# OSER_RFID_RFIDHub.net
KiCad netlist of a schematic drawn in EAGLE
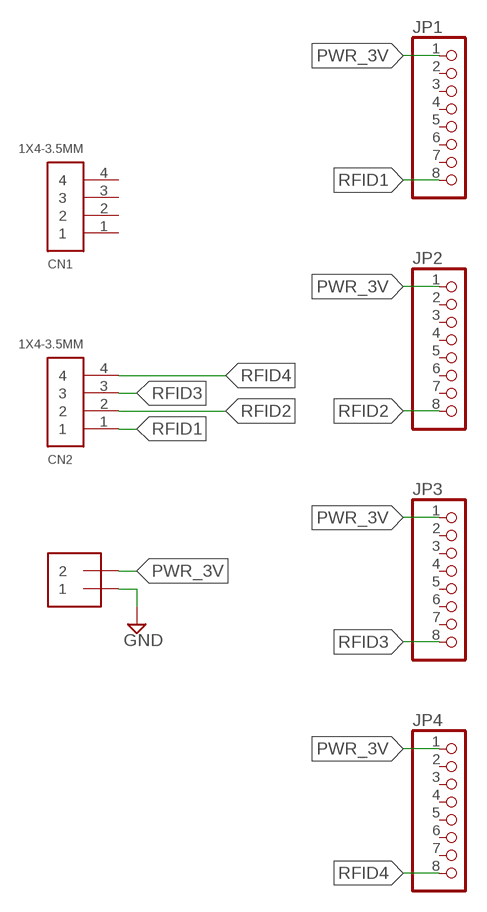
[diagram p0: schematic, sheet 1]

(export (version "E")
  (design (tool "Eeschema 10.0.6"))
  (components
    (comp (ref "CN1")
      (value "1X4-3.5MM")
      (footprint "eagle-import:1X04-3.5MM")
      (libsource (lib "eagle-import") (part "1X4-3.5MM"))
    )
    (comp (ref "CN2")
      (value "1X4-3.5MM")
      (footprint "eagle-import:1X04-3.5MM")
      (libsource (lib "eagle-import") (part "1X4-3.5MM"))
    )
    (comp (ref "J1")
      (value "1X2-3.5MM")
      (footprint "eagle-import:1X2-3.5MM")
      (libsource (lib "eagle-import") (part "1X2-3.5MM"))
    )
    (comp (ref "JP1")
      (value "PINHD-1X8BIG")
      (footprint "eagle-import:1X08-BIG")
      (libsource (lib "eagle-import") (part "PINHD-1X8BIG"))
    )
    (comp (ref "JP2")
      (value "PINHD-1X8BIG")
      (footprint "eagle-import:1X08-BIG")
      (libsource (lib "eagle-import") (part "PINHD-1X8BIG"))
    )
    (comp (ref "JP3")
      (value "PINHD-1X8BIG")
      (footprint "eagle-import:1X08-BIG")
      (libsource (lib "eagle-import") (part "PINHD-1X8BIG"))
    )
    (comp (ref "JP4")
      (value "PINHD-1X8BIG")
      (footprint "eagle-import:1X08-BIG")
      (libsource (lib "eagle-import") (part "PINHD-1X8BIG"))
    )
  )
  (nets
    (net (code "1") (name "GND") (class "Default")
      (node (ref "J1") (pin "1") (pinfunction "1_1") (pintype "passive"))
    )
    (net (code "2") (name "PWR_3V") (class "Default")
      (node (ref "J1") (pin "2") (pinfunction "2_2") (pintype "passive"))
      (node (ref "JP1") (pin "1") (pinfunction "1_1") (pintype "passive"))
      (node (ref "JP2") (pin "1") (pinfunction "1_1") (pintype "passive"))
      (node (ref "JP3") (pin "1") (pinfunction "1_1") (pintype "passive"))
      (node (ref "JP4") (pin "1") (pinfunction "1_1") (pintype "passive"))
    )
    (net (code "3") (name "RFID1") (class "Default")
      (node (ref "CN2") (pin "1") (pinfunction "1_1") (pintype "bidirectional"))
      (node (ref "JP1") (pin "8") (pinfunction "8_8") (pintype "passive"))
    )
    (net (code "4") (name "RFID2") (class "Default")
      (node (ref "CN2") (pin "2") (pinfunction "2_2") (pintype "bidirectional"))
      (node (ref "JP2") (pin "8") (pinfunction "8_8") (pintype "passive"))
    )
    (net (code "5") (name "RFID3") (class "Default")
      (node (ref "CN2") (pin "3") (pinfunction "3_3") (pintype "bidirectional"))
      (node (ref "JP3") (pin "8") (pinfunction "8_8") (pintype "passive"))
    )
    (net (code "6") (name "RFID4") (class "Default")
      (node (ref "CN2") (pin "4") (pinfunction "4_4") (pintype "bidirectional"))
      (node (ref "JP4") (pin "8") (pinfunction "8_8") (pintype "passive"))
    )
    (net (code "7") (name "unconnected-(CN1-Pad1)") (class "Default")
      (node (ref "CN1") (pin "1") (pinfunction "1_1") (pintype "bidirectional"))
    )
    (net (code "8") (name "unconnected-(CN1-Pad2)") (class "Default")
      (node (ref "CN1") (pin "2") (pinfunction "2_2") (pintype "bidirectional"))
    )
    (net (code "9") (name "unconnected-(CN1-Pad3)") (class "Default")
      (node (ref "CN1") (pin "3") (pinfunction "3_3") (pintype "bidirectional"))
    )
    (net (code "10") (name "unconnected-(CN1-Pad4)") (class "Default")
      (node (ref "CN1") (pin "4") (pinfunction "4_4") (pintype "bidirectional"))
    )
    (net (code "11") (name "unconnected-(JP1-Pad2)") (class "Default")
      (node (ref "JP1") (pin "2") (pinfunction "2_2") (pintype "passive"))
    )
    (net (code "12") (name "unconnected-(JP1-Pad3)") (class "Default")
      (node (ref "JP1") (pin "3") (pinfunction "3_3") (pintype "passive"))
    )
    (net (code "13") (name "unconnected-(JP1-Pad4)") (class "Default")
      (node (ref "JP1") (pin "4") (pinfunction "4_4") (pintype "passive"))
    )
    (net (code "14") (name "unconnected-(JP1-Pad5)") (class "Default")
      (node (ref "JP1") (pin "5") (pinfunction "5_5") (pintype "passive"))
    )
    (net (code "15") (name "unconnected-(JP1-Pad6)") (class "Default")
      (node (ref "JP1") (pin "6") (pinfunction "6_6") (pintype "passive"))
    )
    (net (code "16") (name "unconnected-(JP1-Pad7)") (class "Default")
      (node (ref "JP1") (pin "7") (pinfunction "7_7") (pintype "passive"))
    )
    (net (code "17") (name "unconnected-(JP2-Pad2)") (class "Default")
      (node (ref "JP2") (pin "2") (pinfunction "2_2") (pintype "passive"))
    )
    (net (code "18") (name "unconnected-(JP2-Pad3)") (class "Default")
      (node (ref "JP2") (pin "3") (pinfunction "3_3") (pintype "passive"))
    )
    (net (code "19") (name "unconnected-(JP2-Pad4)") (class "Default")
      (node (ref "JP2") (pin "4") (pinfunction "4_4") (pintype "passive"))
    )
    (net (code "20") (name "unconnected-(JP2-Pad5)") (class "Default")
      (node (ref "JP2") (pin "5") (pinfunction "5_5") (pintype "passive"))
    )
    (net (code "21") (name "unconnected-(JP2-Pad6)") (class "Default")
      (node (ref "JP2") (pin "6") (pinfunction "6_6") (pintype "passive"))
    )
    (net (code "22") (name "unconnected-(JP2-Pad7)") (class "Default")
      (node (ref "JP2") (pin "7") (pinfunction "7_7") (pintype "passive"))
    )
    (net (code "23") (name "unconnected-(JP3-Pad2)") (class "Default")
      (node (ref "JP3") (pin "2") (pinfunction "2_2") (pintype "passive"))
    )
    (net (code "24") (name "unconnected-(JP3-Pad3)") (class "Default")
      (node (ref "JP3") (pin "3") (pinfunction "3_3") (pintype "passive"))
    )
    (net (code "25") (name "unconnected-(JP3-Pad4)") (class "Default")
      (node (ref "JP3") (pin "4") (pinfunction "4_4") (pintype "passive"))
    )
    (net (code "26") (name "unconnected-(JP3-Pad5)") (class "Default")
      (node (ref "JP3") (pin "5") (pinfunction "5_5") (pintype "passive"))
    )
    (net (code "27") (name "unconnected-(JP3-Pad6)") (class "Default")
      (node (ref "JP3") (pin "6") (pinfunction "6_6") (pintype "passive"))
    )
    (net (code "28") (name "unconnected-(JP3-Pad7)") (class "Default")
      (node (ref "JP3") (pin "7") (pinfunction "7_7") (pintype "passive"))
    )
    (net (code "29") (name "unconnected-(JP4-Pad2)") (class "Default")
      (node (ref "JP4") (pin "2") (pinfunction "2_2") (pintype "passive"))
    )
    (net (code "30") (name "unconnected-(JP4-Pad3)") (class "Default")
      (node (ref "JP4") (pin "3") (pinfunction "3_3") (pintype "passive"))
    )
    (net (code "31") (name "unconnected-(JP4-Pad4)") (class "Default")
      (node (ref "JP4") (pin "4") (pinfunction "4_4") (pintype "passive"))
    )
    (net (code "32") (name "unconnected-(JP4-Pad5)") (class "Default")
      (node (ref "JP4") (pin "5") (pinfunction "5_5") (pintype "passive"))
    )
    (net (code "33") (name "unconnected-(JP4-Pad6)") (class "Default")
      (node (ref "JP4") (pin "6") (pinfunction "6_6") (pintype "passive"))
    )
    (net (code "34") (name "unconnected-(JP4-Pad7)") (class "Default")
      (node (ref "JP4") (pin "7") (pinfunction "7_7") (pintype "passive"))
    )
  )
)
